# VProbe.net
KiCad netlist of a schematic drawn in EAGLE
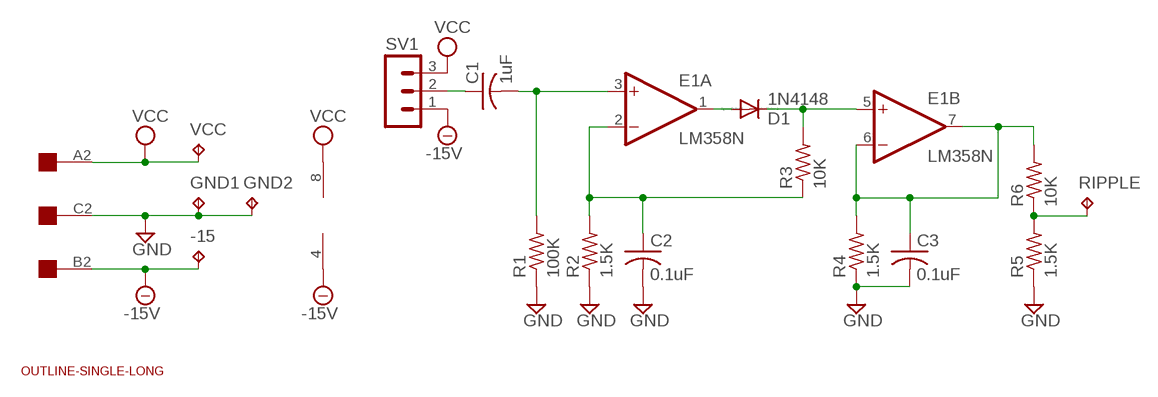
[diagram p0: schematic, sheet 1]

(export (version "E")
  (design (tool "Eeschema 10.0.6"))
  (components
    (comp (ref "-15")
      (value "TPPAD1-13")
      (footprint "eagle-import:P1-13")
      (libsource (lib "eagle-import") (part "TPPAD1-13"))
    )
    (comp (ref "C1")
      (value "1uF")
      (footprint "eagle-import:C075-032X103")
      (libsource (lib "eagle-import") (part "C-US075-032X103"))
    )
    (comp (ref "C2")
      (value "0.1uF")
      (footprint "eagle-import:C075-032X103")
      (libsource (lib "eagle-import") (part "C-US075-032X103"))
    )
    (comp (ref "C3")
      (value "0.1uF")
      (footprint "eagle-import:C075-032X103")
      (libsource (lib "eagle-import") (part "C-US075-032X103"))
    )
    (comp (ref "D1")
      (value "1N4148")
      (footprint "eagle-import:DO35-10")
      (libsource (lib "eagle-import") (part "DIODE-DO35-10"))
    )
    (comp (ref "E1")
      (value "LM358N")
      (footprint "eagle-import:DIL08")
      (libsource (lib "eagle-import") (part "LM358N"))
    )
    (comp (ref "GND1")
      (value "TPPAD1-13")
      (footprint "eagle-import:P1-13")
      (libsource (lib "eagle-import") (part "TPPAD1-13"))
    )
    (comp (ref "GND2")
      (value "TPPAD1-13")
      (footprint "eagle-import:P1-13")
      (libsource (lib "eagle-import") (part "TPPAD1-13"))
    )
    (comp (ref "R1")
      (value "100K")
      (footprint "eagle-import:0207_10")
      (libsource (lib "eagle-import") (part "R-US_0207/10"))
    )
    (comp (ref "R2")
      (value "1.5K")
      (footprint "eagle-import:0207_10")
      (libsource (lib "eagle-import") (part "R-US_0207/10"))
    )
    (comp (ref "R3")
      (value "10K")
      (footprint "eagle-import:0207_10")
      (libsource (lib "eagle-import") (part "R-US_0207/10"))
    )
    (comp (ref "R4")
      (value "1.5K")
      (footprint "eagle-import:0207_10")
      (libsource (lib "eagle-import") (part "R-US_0207/10"))
    )
    (comp (ref "R5")
      (value "1.5K")
      (footprint "eagle-import:0207_10")
      (libsource (lib "eagle-import") (part "R-US_0207/10"))
    )
    (comp (ref "R6")
      (value "10K")
      (footprint "eagle-import:0207_10")
      (libsource (lib "eagle-import") (part "R-US_0207/10"))
    )
    (comp (ref "RIPPLE")
      (value "TPPAD1-13")
      (footprint "eagle-import:P1-13")
      (libsource (lib "eagle-import") (part "TPPAD1-13"))
    )
    (comp (ref "SV1")
      (value "MA03-1")
      (footprint "eagle-import:MA03-1")
      (libsource (lib "eagle-import") (part "MA03-1"))
    )
    (comp (ref "U$1")
      (value "EDGE-1")
      (footprint "eagle-import:EDGE-CON1")
      (libsource (lib "eagle-import") (part "EDGE-1"))
    )
    (comp (ref "U$2")
      (value "OUTLINE-SINGLE-LONG")
      (footprint "eagle-import:SINGLE-LONG")
      (libsource (lib "eagle-import") (part "OUTLINE-SINGLE-LONG"))
    )
    (comp (ref "VCC")
      (value "TPPAD1-13")
      (footprint "eagle-import:P1-13")
      (libsource (lib "eagle-import") (part "TPPAD1-13"))
    )
  )
  (nets
    (net (code "1") (name "-15V") (class "Default")
      (node (ref "-15") (pin "TP") (pinfunction "TP_TP") (pintype "input"))
      (node (ref "E1") (pin "4") (pinfunction "V-_4") (pintype "power_in"))
      (node (ref "SV1") (pin "1") (pinfunction "1_1") (pintype "passive"))
      (node (ref "U$1") (pin "B2") (pinfunction "1_B2") (pintype "bidirectional"))
    )
    (net (code "2") (name "GND") (class "Default")
      (node (ref "C2") (pin "2") (pinfunction "2_2") (pintype "passive"))
      (node (ref "C3") (pin "2") (pinfunction "2_2") (pintype "passive"))
      (node (ref "GND1") (pin "TP") (pinfunction "TP_TP") (pintype "input"))
      (node (ref "GND2") (pin "TP") (pinfunction "TP_TP") (pintype "input"))
      (node (ref "R1") (pin "1") (pinfunction "1_1") (pintype "passive"))
      (node (ref "R2") (pin "1") (pinfunction "1_1") (pintype "passive"))
      (node (ref "R4") (pin "1") (pinfunction "1_1") (pintype "passive"))
      (node (ref "R5") (pin "1") (pinfunction "1_1") (pintype "passive"))
      (node (ref "U$1") (pin "C2") (pinfunction "1_C2") (pintype "bidirectional"))
    )
    (net (code "3") (name "Net-(C1-Pad1)") (class "Default")
      (node (ref "C1") (pin "1") (pinfunction "1_1") (pintype "passive"))
      (node (ref "SV1") (pin "2") (pinfunction "2_2") (pintype "passive"))
    )
    (net (code "4") (name "Net-(E1A-+IN)") (class "Default")
      (node (ref "C1") (pin "2") (pinfunction "2_2") (pintype "passive"))
      (node (ref "E1") (pin "3") (pinfunction "+IN_3") (pintype "input"))
      (node (ref "R1") (pin "2") (pinfunction "2_2") (pintype "passive"))
    )
    (net (code "5") (name "Net-(E1A--IN)") (class "Default")
      (node (ref "C2") (pin "1") (pinfunction "1_1") (pintype "passive"))
      (node (ref "E1") (pin "2") (pinfunction "-IN_2") (pintype "input"))
      (node (ref "R2") (pin "2") (pinfunction "2_2") (pintype "passive"))
      (node (ref "R3") (pin "1") (pinfunction "1_1") (pintype "passive"))
    )
    (net (code "6") (name "Net-(E1A-OUT)") (class "Default")
      (node (ref "D1") (pin "A") (pinfunction "A_A") (pintype "passive"))
      (node (ref "E1") (pin "1") (pinfunction "OUT_1") (pintype "output"))
    )
    (net (code "7") (name "Net-(E1B-+IN)") (class "Default")
      (node (ref "D1") (pin "C") (pinfunction "C_C") (pintype "passive"))
      (node (ref "E1") (pin "5") (pinfunction "+IN_5") (pintype "input"))
      (node (ref "R3") (pin "2") (pinfunction "2_2") (pintype "passive"))
    )
    (net (code "8") (name "Net-(E1B--IN)") (class "Default")
      (node (ref "C3") (pin "1") (pinfunction "1_1") (pintype "passive"))
      (node (ref "E1") (pin "6") (pinfunction "-IN_6") (pintype "input"))
      (node (ref "E1") (pin "7") (pinfunction "OUT_7") (pintype "output"))
      (node (ref "R4") (pin "2") (pinfunction "2_2") (pintype "passive"))
      (node (ref "R6") (pin "2") (pinfunction "2_2") (pintype "passive"))
    )
    (net (code "9") (name "Net-(R5-Pad2)") (class "Default")
      (node (ref "R5") (pin "2") (pinfunction "2_2") (pintype "passive"))
      (node (ref "R6") (pin "1") (pinfunction "1_1") (pintype "passive"))
      (node (ref "RIPPLE") (pin "TP") (pinfunction "TP_TP") (pintype "input"))
    )
    (net (code "10") (name "VCC") (class "Default")
      (node (ref "E1") (pin "8") (pinfunction "V+_8") (pintype "power_in"))
      (node (ref "SV1") (pin "3") (pinfunction "3_3") (pintype "passive"))
      (node (ref "U$1") (pin "A2") (pinfunction "1_A2") (pintype "bidirectional"))
      (node (ref "VCC") (pin "TP") (pinfunction "TP_TP") (pintype "input"))
    )
  )
)
